# Top.net
KiCad netlist of a schematic drawn in Altium Designer
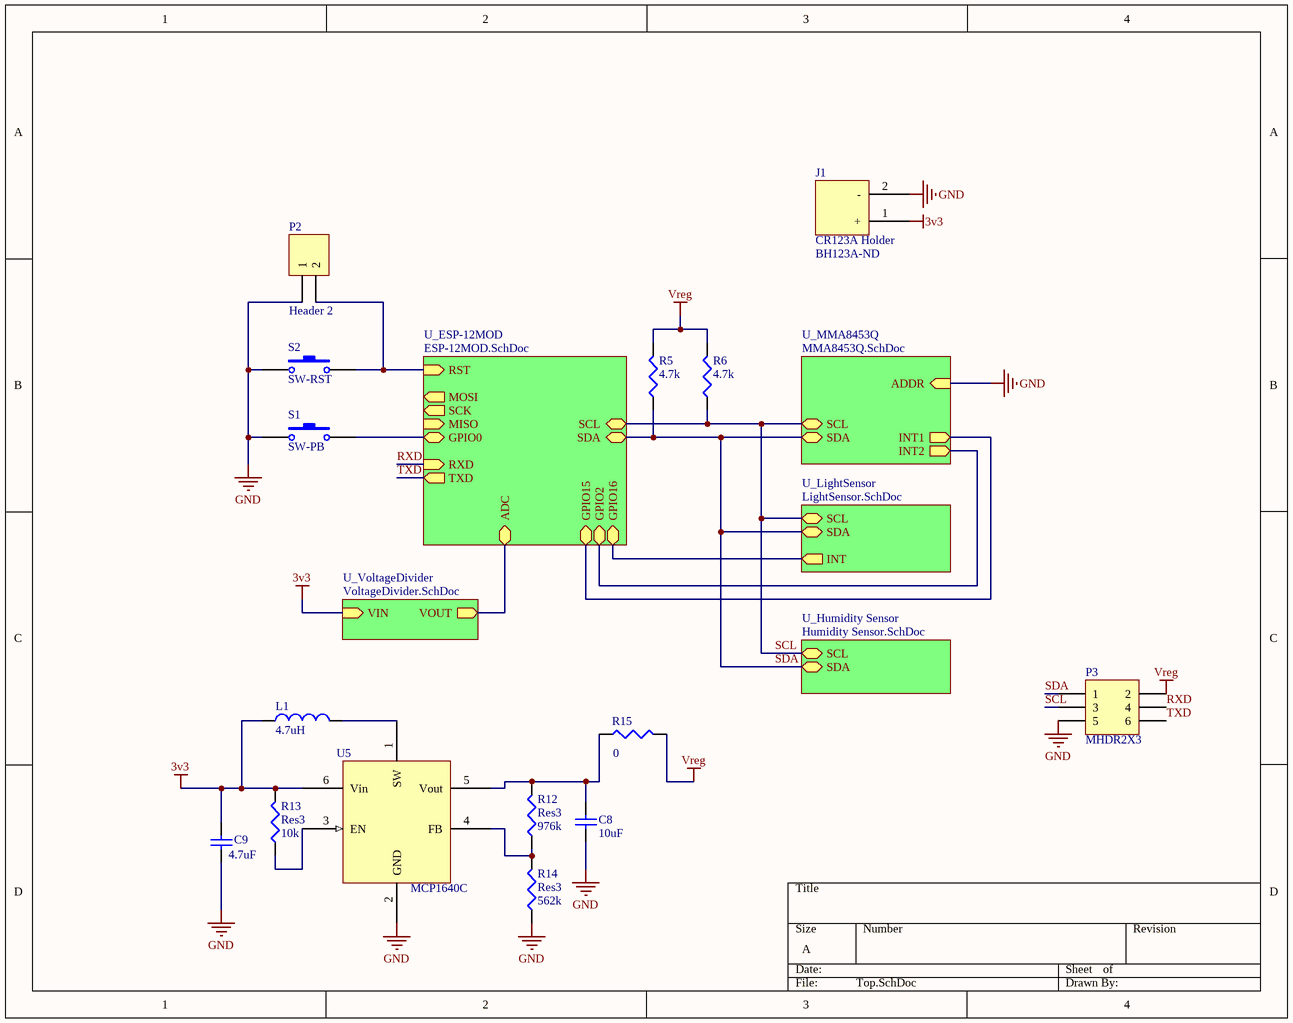
[diagram p0: Top.SchDoc]

(export (version "E")
  (design (tool "Eeschema 10.0.6"))
  (components
    (comp (ref "C8")
      (value "10uF")
      (footprint "C0805")
      (description "Capacitor")
      (fields (field (name "Comment") "Cap") (field (name "PUBLISHER") "Altium Limited"))
      (libsource (lib "Miscellaneous Devices") (part "Cap"))
    )
    (comp (ref "C9")
      (value "4.7uF")
      (footprint "C0805")
      (description "Capacitor")
      (fields (field (name "Comment") "Cap") (field (name "PUBLISHER") "Altium Limited"))
      (libsource (lib "Miscellaneous Devices") (part "Cap"))
    )
    (comp (ref "J1")
      (value "CR123A Holder")
      (footprint "BHA123A")
      (fields (field (name "SUPPLIER PART NUMBER 1") "BH123A-ND"))
      (libsource (lib "Miscellaneous Connectors") (part "CR123A Holder"))
    )
    (comp (ref "L1")
      (value "4.7uH")
      (footprint "6.3mmx6.3mm Inductor")
      (description "Inductor")
      (fields (field (name "PUBLISHER") "Altium Limited"))
      (libsource (lib "Miscellaneous Devices") (part "Inductor"))
    )
    (comp (ref "P2")
      (value "Header 2")
      (footprint "HDR1X2")
      (description "Header, 2-Pin")
      (fields (field (name "PUBLISHER") "Altium Limited"))
      (libsource (lib "Miscellaneous Connectors") (part "Header 2"))
    )
    (comp (ref "P3")
      (value "MHDR2X3")
      (footprint "MHDR2X3")
      (description "Header, 3-Pin, Dual row")
      (fields (field (name "PUBLISHER") "Altium Limited"))
      (libsource (lib "Miscellaneous Connectors") (part "MHDR2X3"))
    )
    (comp (ref "R5")
      (value "4.7k")
      (footprint "J1-0603")
      (description "Resistor")
      (fields (field (name "Comment") "Res3") (field (name "PUBLISHER") "Altium Limited"))
      (libsource (lib "Miscellaneous Devices") (part "Res3"))
    )
    (comp (ref "R6")
      (value "4.7k")
      (footprint "J1-0603")
      (description "Resistor")
      (fields (field (name "Comment") "Res3") (field (name "PUBLISHER") "Altium Limited"))
      (libsource (lib "Miscellaneous Devices") (part "Res3"))
    )
    (comp (ref "R12")
      (value "Res3")
      (footprint "J1-0603")
      (description "Resistor")
      (fields (field (name "ALTIUM_VALUE") "976k") (field (name "PUBLISHER") "Altium Limited"))
      (libsource (lib "Miscellaneous Devices") (part "Res3"))
    )
    (comp (ref "R13")
      (value "Res3")
      (footprint "J1-0603")
      (description "Resistor")
      (fields (field (name "ALTIUM_VALUE") "10k") (field (name "PUBLISHER") "Altium Limited"))
      (libsource (lib "Miscellaneous Devices") (part "Res3"))
    )
    (comp (ref "R14")
      (value "Res3")
      (footprint "J1-0603")
      (description "Resistor")
      (fields (field (name "ALTIUM_VALUE") "562k") (field (name "PUBLISHER") "Altium Limited"))
      (libsource (lib "Miscellaneous Devices") (part "Res3"))
    )
    (comp (ref "R15")
      (value "0")
      (footprint "J1-0603")
      (description "Resistor")
      (fields (field (name "Comment") "Res3") (field (name "PUBLISHER") "Altium Limited"))
      (libsource (lib "Miscellaneous Devices") (part "Res3"))
    )
    (comp (ref "S1")
      (value "SW-PB")
      (footprint "SMD SPST Tactile Switch")
      (description "Switch")
      (fields (field (name "PUBLISHER") "Altium Limited"))
      (libsource (lib "Miscellaneous Devices") (part "SW-PB"))
    )
    (comp (ref "S2")
      (value "SW-RST")
      (footprint "SMD SPST Tactile Switch")
      (description "Switch")
      (fields (field (name "PUBLISHER") "Altium Limited"))
      (libsource (lib "Miscellaneous Devices") (part "SW-PB"))
    )
    (comp (ref "U5")
      (value "MCP1640C")
      (footprint "SOT-23 MCP1640")
      (description "Synchronous Boost converter 100mA")
      (libsource (lib "Miscellaneous Devices") (part "MCP1640C"))
    )
  )
  (nets
    (net (code "1") (name "/GPIO0") (class "Default")
      (node (ref "S1") (pin "2") (pinfunction "2_2") (pintype "passive"))
    )
    (net (code "7") (name "/RST") (class "Default")
      (node (ref "P2") (pin "2") (pinfunction "2_2") (pintype "passive"))
      (node (ref "S2") (pin "2") (pinfunction "2_2") (pintype "passive"))
    )
    (net (code "8") (name "/RXD") (class "Default")
      (node (ref "P3") (pin "4") (pinfunction "4_4") (pintype "passive"))
    )
    (net (code "10") (name "/SCL") (class "Default")
      (node (ref "P3") (pin "3") (pinfunction "3_3") (pintype "passive"))
      (node (ref "R6") (pin "1") (pinfunction "1_1") (pintype "passive"))
    )
    (net (code "11") (name "/SDA") (class "Default")
      (node (ref "P3") (pin "1") (pinfunction "1_1") (pintype "passive"))
      (node (ref "R5") (pin "1") (pinfunction "1_1") (pintype "passive"))
    )
    (net (code "12") (name "/TXD") (class "Default")
      (node (ref "P3") (pin "6") (pinfunction "6_6") (pintype "passive"))
    )
    (net (code "14") (name "3v3") (class "Default")
      (node (ref "C9") (pin "2") (pinfunction "2_2") (pintype "passive"))
      (node (ref "J1") (pin "1") (pinfunction "+_1") (pintype "power_in"))
      (node (ref "L1") (pin "1") (pinfunction "1_1") (pintype "passive"))
      (node (ref "R13") (pin "2") (pinfunction "2_2") (pintype "passive"))
      (node (ref "U5") (pin "6") (pinfunction "Vin_6") (pintype "power_in"))
    )
    (net (code "15") (name "GND") (class "Default")
      (node (ref "C8") (pin "1") (pinfunction "1_1") (pintype "passive"))
      (node (ref "C9") (pin "1") (pinfunction "1_1") (pintype "passive"))
      (node (ref "J1") (pin "2") (pinfunction "-_2") (pintype "power_in"))
      (node (ref "P2") (pin "1") (pinfunction "1_1") (pintype "passive"))
      (node (ref "P3") (pin "5") (pinfunction "5_5") (pintype "passive"))
      (node (ref "R14") (pin "1") (pinfunction "1_1") (pintype "passive"))
      (node (ref "S1") (pin "1") (pinfunction "1_1") (pintype "passive"))
      (node (ref "S2") (pin "1") (pinfunction "1_1") (pintype "passive"))
      (node (ref "U5") (pin "2") (pinfunction "GND_2") (pintype "power_in"))
    )
    (net (code "16") (name "Net-(U5-EN)") (class "Default")
      (node (ref "R13") (pin "1") (pinfunction "1_1") (pintype "passive"))
      (node (ref "U5") (pin "3") (pinfunction "EN_3") (pintype "input"))
    )
    (net (code "17") (name "Net-(U5-FB)") (class "Default")
      (node (ref "R12") (pin "1") (pinfunction "1_1") (pintype "passive"))
      (node (ref "R14") (pin "2") (pinfunction "2_2") (pintype "passive"))
      (node (ref "U5") (pin "4") (pinfunction "FB_4") (pintype "passive"))
    )
    (net (code "18") (name "Net-(U5-SW)") (class "Default")
      (node (ref "L1") (pin "2") (pinfunction "2_2") (pintype "passive"))
      (node (ref "U5") (pin "1") (pinfunction "SW_1") (pintype "power_in"))
    )
    (net (code "19") (name "Net-(U5-Vout)") (class "Default")
      (node (ref "C8") (pin "2") (pinfunction "2_2") (pintype "passive"))
      (node (ref "R12") (pin "2") (pinfunction "2_2") (pintype "passive"))
      (node (ref "R15") (pin "1") (pinfunction "1_1") (pintype "passive"))
      (node (ref "U5") (pin "5") (pinfunction "Vout_5") (pintype "power_in"))
    )
    (net (code "20") (name "Vreg") (class "Default")
      (node (ref "P3") (pin "2") (pinfunction "2_2") (pintype "passive"))
      (node (ref "R15") (pin "2") (pinfunction "2_2") (pintype "passive"))
      (node (ref "R5") (pin "2") (pinfunction "2_2") (pintype "passive"))
      (node (ref "R6") (pin "2") (pinfunction "2_2") (pintype "passive"))
    )
  )
)
